# DC-Motor-DRV.net
KiCad netlist of a schematic drawn in Altium Designer
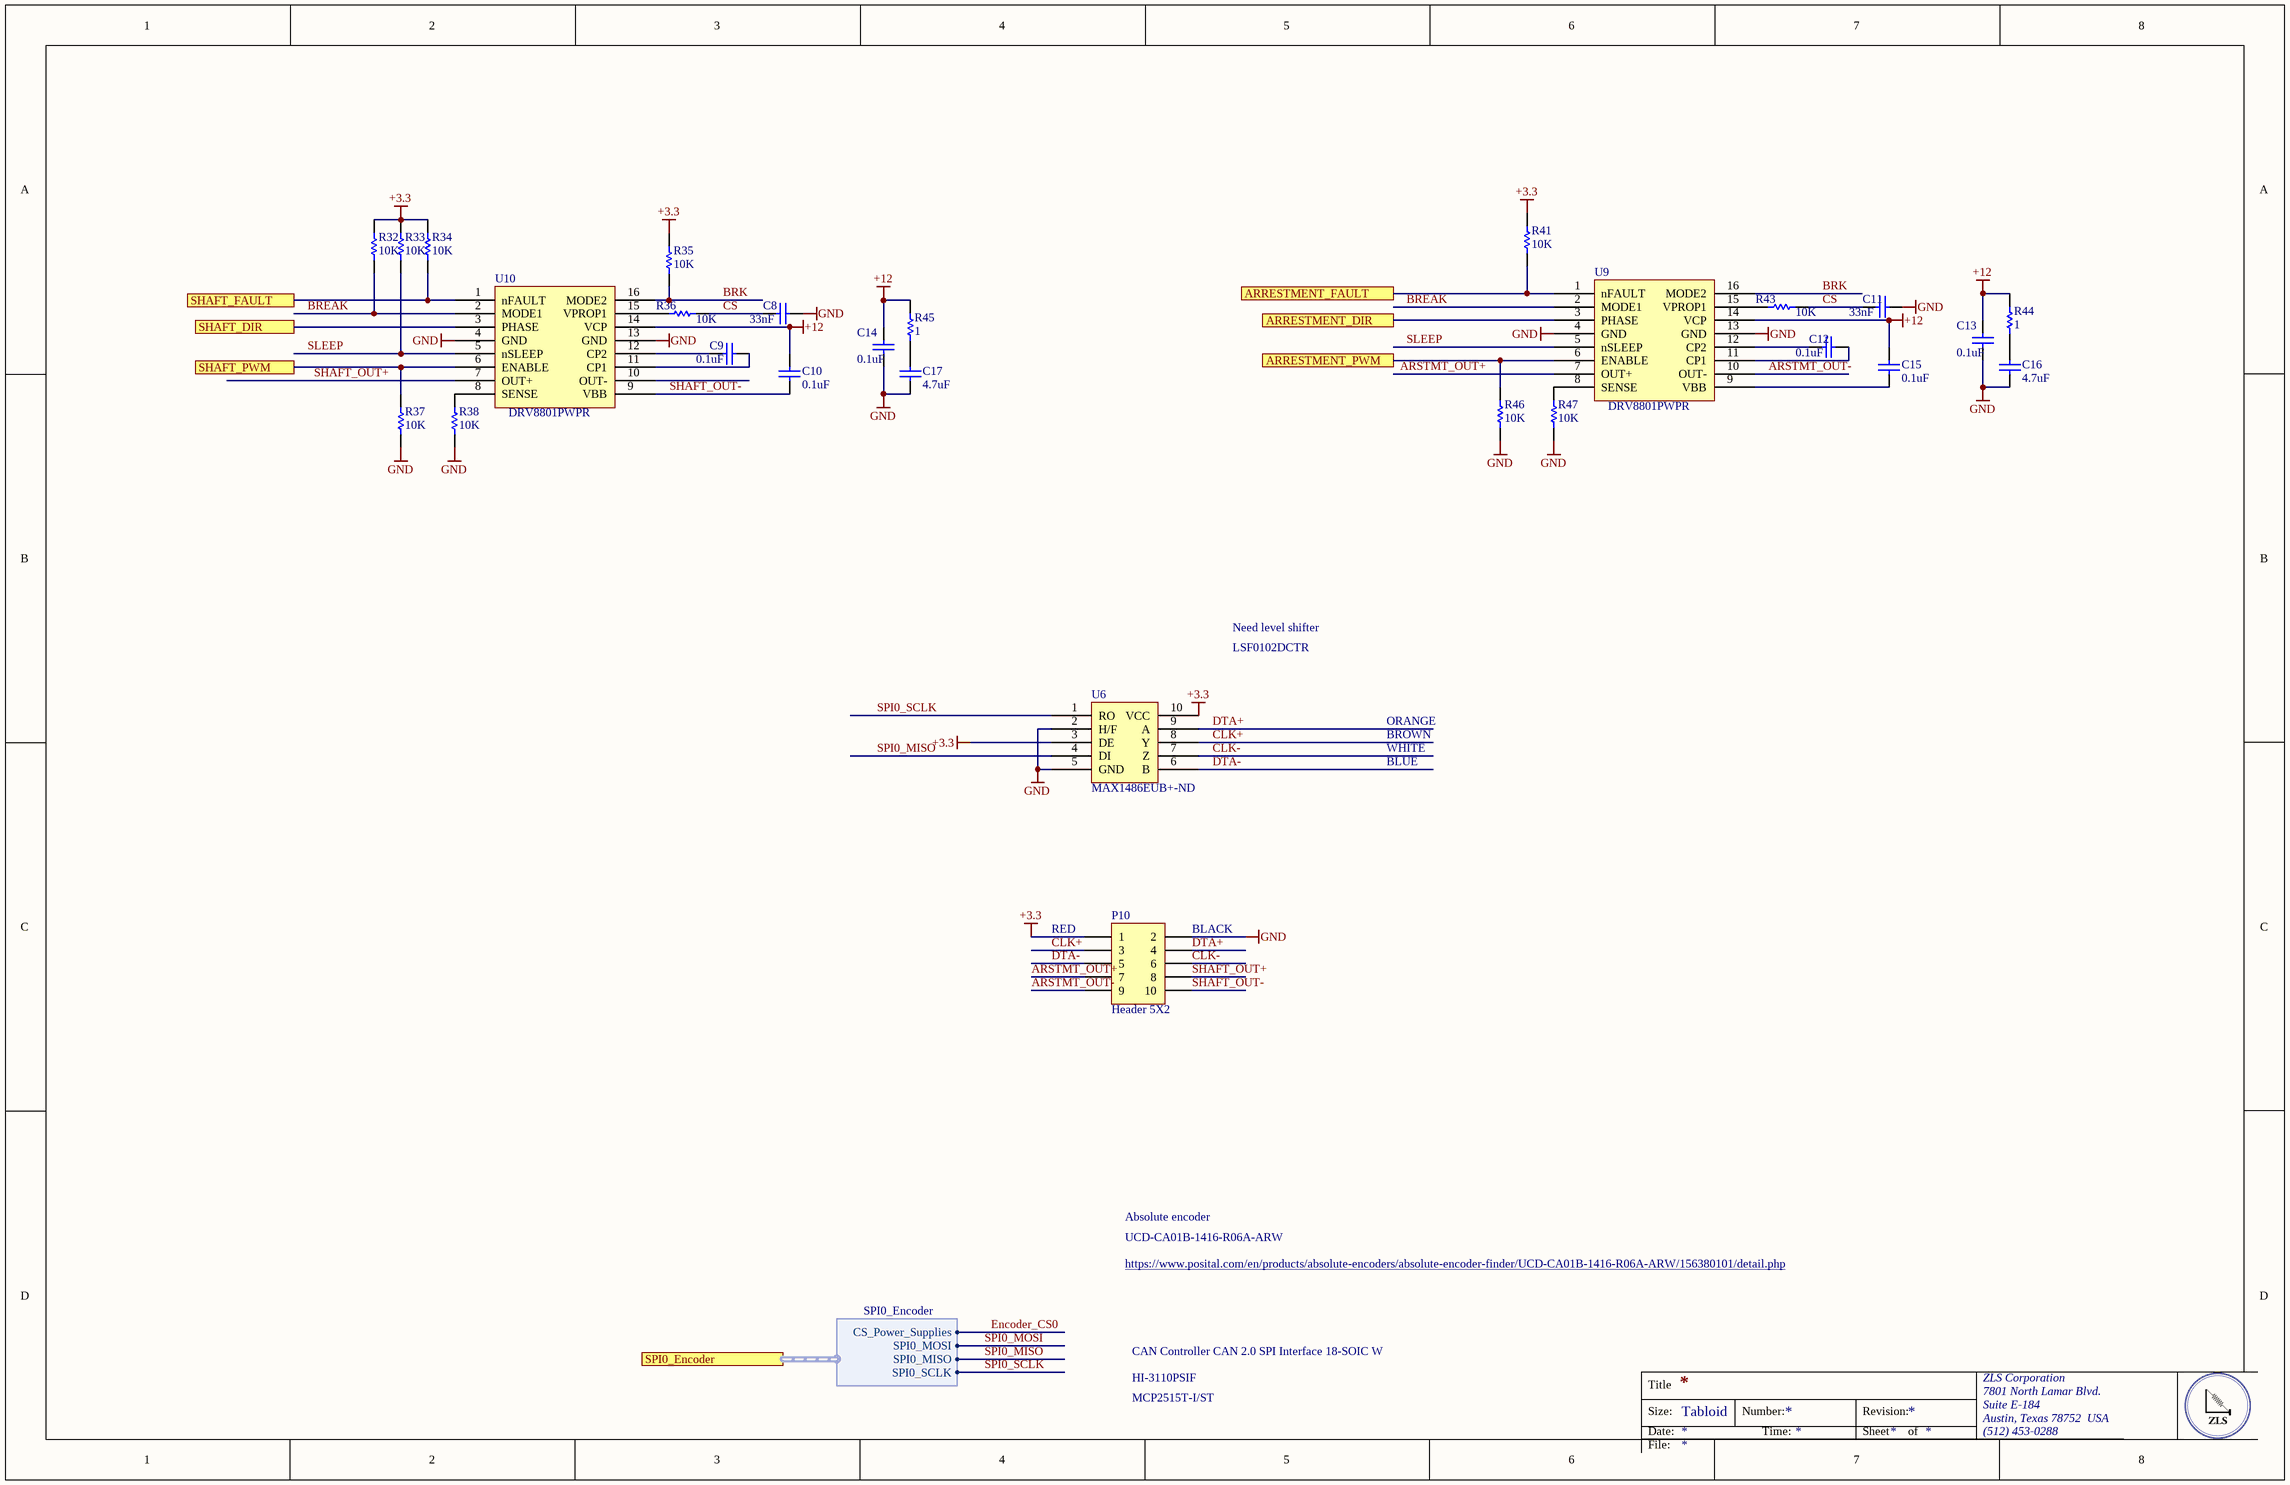
[diagram p0: DC-Motor-DRV.SchDoc]

(export (version "E")
  (design (tool "Eeschema 10.0.6"))
  (components
    (comp (ref "C8")
      (value "33nF")
      (footprint "CAPC0402(1005)60_L")
      (description "CAP CER 0.1UF 10V X7R 0402")
      (fields
        (field (name "MANUFACTURER") "Murata Electronics North America")
        (field (name "MANUFACTURER PART NUMBER") "GRM155R71A104KA01D")
      )
      (libsource (lib "Altium Content Vault") (part "CMP-1034-00252-1"))
    )
    (comp (ref "C9")
      (value "0.1uF")
      (footprint "CAPC0402(1005)60_L")
      (description "CAP CER 0.1UF 10V X7R 0402")
      (fields
        (field (name "MANUFACTURER") "Murata Electronics North America")
        (field (name "MANUFACTURER PART NUMBER") "GRM155R71A104KA01D")
      )
      (libsource (lib "Altium Content Vault") (part "CMP-1034-00252-1"))
    )
    (comp (ref "C10")
      (value "0.1uF")
      (footprint "CAPC0402(1005)60_L")
      (description "CAP CER 0.1UF 10V X7R 0402")
      (fields
        (field (name "MANUFACTURER") "Murata Electronics North America")
        (field (name "MANUFACTURER PART NUMBER") "GRM155R71A104KA01D")
      )
      (libsource (lib "Altium Content Vault") (part "CMP-1034-00252-1"))
    )
    (comp (ref "C11")
      (value "33nF")
      (footprint "CAPC0402(1005)60_L")
      (description "CAP CER 0.1UF 10V X7R 0402")
      (fields
        (field (name "MANUFACTURER") "Murata Electronics North America")
        (field (name "MANUFACTURER PART NUMBER") "GRM155R71A104KA01D")
      )
      (libsource (lib "Altium Content Vault") (part "CMP-1034-00252-1"))
    )
    (comp (ref "C12")
      (value "0.1uF")
      (footprint "CAPC0402(1005)60_L")
      (description "CAP CER 0.1UF 10V X7R 0402")
      (fields
        (field (name "MANUFACTURER") "Murata Electronics North America")
        (field (name "MANUFACTURER PART NUMBER") "GRM155R71A104KA01D")
      )
      (libsource (lib "Altium Content Vault") (part "CMP-1034-00252-1"))
    )
    (comp (ref "C13")
      (value "0.1uF")
      (footprint "CAPC0402(1005)60_L")
      (description "CAP CER 0.1UF 10V X7R 0402")
      (fields
        (field (name "MANUFACTURER") "Murata Electronics North America")
        (field (name "MANUFACTURER PART NUMBER") "GRM155R71A104KA01D")
      )
      (libsource (lib "Altium Content Vault") (part "CMP-1034-00252-1"))
    )
    (comp (ref "C14")
      (value "0.1uF")
      (footprint "CAPC0402(1005)60_L")
      (description "CAP CER 0.1UF 10V X7R 0402")
      (fields
        (field (name "MANUFACTURER") "Murata Electronics North America")
        (field (name "MANUFACTURER PART NUMBER") "GRM155R71A104KA01D")
      )
      (libsource (lib "Altium Content Vault") (part "CMP-1034-00252-1"))
    )
    (comp (ref "C15")
      (value "0.1uF")
      (footprint "CAPC0402(1005)60_L")
      (description "CAP CER 0.1UF 10V X7R 0402")
      (fields
        (field (name "MANUFACTURER") "Murata Electronics North America")
        (field (name "MANUFACTURER PART NUMBER") "GRM155R71A104KA01D")
      )
      (libsource (lib "Altium Content Vault") (part "CMP-1034-00252-1"))
    )
    (comp (ref "C16")
      (value "4.7uF")
      (footprint "CAPC0402(1005)60_L")
      (description "CAP CER 0.1UF 10V X7R 0402")
      (fields
        (field (name "MANUFACTURER") "Murata Electronics North America")
        (field (name "MANUFACTURER PART NUMBER") "GRM155R71A104KA01D")
      )
      (libsource (lib "Altium Content Vault") (part "CMP-1034-00252-1"))
    )
    (comp (ref "C17")
      (value "4.7uF")
      (footprint "CAPC0402(1005)60_L")
      (description "CAP CER 0.1UF 10V X7R 0402")
      (fields
        (field (name "MANUFACTURER") "Murata Electronics North America")
        (field (name "MANUFACTURER PART NUMBER") "GRM155R71A104KA01D")
      )
      (libsource (lib "Altium Content Vault") (part "CMP-1034-00252-1"))
    )
    (comp (ref "P10")
      (value "Header 5X2")
      (footprint "HDR2X5")
      (description "Header, 5-Pin, Dual row")
      (fields (field (name "PUBLISHER") "Altium Limited"))
      (libsource (lib "Miscellaneous Connectors") (part "Header 5X2"))
    )
    (comp (ref "R32")
      (value "10K")
      (footprint "RESC0402(1005)_M")
      (libsource (lib "Altium Content Vault") (part "CMP-1011-00651-1"))
    )
    (comp (ref "R33")
      (value "10K")
      (footprint "RESC0402(1005)_M")
      (libsource (lib "Altium Content Vault") (part "CMP-1011-00651-1"))
    )
    (comp (ref "R34")
      (value "10K")
      (footprint "RESC0402(1005)_M")
      (libsource (lib "Altium Content Vault") (part "CMP-1011-00651-1"))
    )
    (comp (ref "R35")
      (value "10K")
      (footprint "RESC0402(1005)_M")
      (libsource (lib "Altium Content Vault") (part "CMP-1011-00651-1"))
    )
    (comp (ref "R36")
      (value "10K")
      (footprint "RESC0402(1005)_M")
      (libsource (lib "Altium Content Vault") (part "CMP-1011-00651-1"))
    )
    (comp (ref "R37")
      (value "10K")
      (footprint "RESC0402(1005)_M")
      (libsource (lib "Altium Content Vault") (part "CMP-1011-00651-1"))
    )
    (comp (ref "R38")
      (value "10K")
      (footprint "RESC0402(1005)_M")
      (libsource (lib "Altium Content Vault") (part "CMP-1011-00651-1"))
    )
    (comp (ref "R41")
      (value "10K")
      (footprint "RESC0402(1005)_M")
      (libsource (lib "Altium Content Vault") (part "CMP-1011-00651-1"))
    )
    (comp (ref "R43")
      (value "10K")
      (footprint "RESC0402(1005)_M")
      (libsource (lib "Altium Content Vault") (part "CMP-1011-00651-1"))
    )
    (comp (ref "R44")
      (value "1")
      (footprint "RESC0402(1005)_M")
      (libsource (lib "Altium Content Vault") (part "CMP-1011-00651-1"))
    )
    (comp (ref "R45")
      (value "1")
      (footprint "RESC0402(1005)_M")
      (libsource (lib "Altium Content Vault") (part "CMP-1011-00651-1"))
    )
    (comp (ref "R46")
      (value "10K")
      (footprint "RESC0402(1005)_M")
      (libsource (lib "Altium Content Vault") (part "CMP-1011-00651-1"))
    )
    (comp (ref "R47")
      (value "10K")
      (footprint "RESC0402(1005)_M")
      (libsource (lib "Altium Content Vault") (part "CMP-1011-00651-1"))
    )
    (comp (ref "U6")
      (value "MAX1486EUB+")
      (footprint "MAX1486EUB+")
      (fields
        (field (name "SUPPLIER PART NUMBER 1") "MAX1486EUB+-ND")
        (field (name "MANUFACTURER") "Maxim Integrated")
        (field (name "BASE PART NUMBER") "MAX1486")
      )
      (libsource (lib "ZLS_Schematic_lib") (part "MAX1486EUB+"))
    )
    (comp (ref "U9")
      (value "DRV8801PWPR")
      (footprint "DRV8801PWPR")
      (fields (field (name "MANUFACTURER") "Texas Instruments") (field (name "BASE PART NUMBER") "DRV8801"))
      (libsource (lib "ZLS_Schematic_lib") (part "DRV8801PWPR"))
    )
    (comp (ref "U10")
      (value "DRV8801PWPR")
      (footprint "DRV8801PWPR")
      (fields (field (name "MANUFACTURER") "Texas Instruments") (field (name "BASE PART NUMBER") "DRV8801"))
      (libsource (lib "ZLS_Schematic_lib") (part "DRV8801PWPR"))
    )
  )
  (nets
    (net (code "2") (name "+3.3") (class "Default")
      (node (ref "P10") (pin "1") (pinfunction "1_1") (pintype "passive"))
      (node (ref "R32") (pin "2") (pinfunction "2_2") (pintype "passive"))
      (node (ref "R33") (pin "2") (pinfunction "2_2") (pintype "passive"))
      (node (ref "R34") (pin "2") (pinfunction "2_2") (pintype "passive"))
      (node (ref "R35") (pin "2") (pinfunction "2_2") (pintype "passive"))
      (node (ref "R41") (pin "2") (pinfunction "2_2") (pintype "passive"))
      (node (ref "U6") (pin "10") (pinfunction "VCC_10") (pintype "passive"))
      (node (ref "U6") (pin "3") (pinfunction "DE_3") (pintype "passive"))
    )
    (net (code "3") (name "+12") (class "Default")
      (node (ref "C10") (pin "2") (pinfunction "2_2") (pintype "passive"))
      (node (ref "C13") (pin "2") (pinfunction "2_2") (pintype "passive"))
      (node (ref "C14") (pin "2") (pinfunction "2_2") (pintype "passive"))
      (node (ref "C15") (pin "2") (pinfunction "2_2") (pintype "passive"))
      (node (ref "R44") (pin "2") (pinfunction "2_2") (pintype "passive"))
      (node (ref "R45") (pin "2") (pinfunction "2_2") (pintype "passive"))
      (node (ref "U10") (pin "14") (pinfunction "VCP_14") (pintype "passive"))
      (node (ref "U9") (pin "14") (pinfunction "VCP_14") (pintype "passive"))
    )
    (net (code "4") (name "/ARRESTMENT_DIR") (class "Default")
      (node (ref "U9") (pin "3") (pinfunction "PHASE_3") (pintype "passive"))
    )
    (net (code "5") (name "/ARRESTMENT_FAULT") (class "Default")
      (node (ref "R41") (pin "1") (pinfunction "1_1") (pintype "passive"))
      (node (ref "U9") (pin "1") (pinfunction "nFAULT_1") (pintype "passive"))
    )
    (net (code "6") (name "/ARRESTMENT_PWM") (class "Default")
      (node (ref "R46") (pin "2") (pinfunction "2_2") (pintype "passive"))
      (node (ref "U9") (pin "6") (pinfunction "ENABLE_6") (pintype "passive"))
    )
    (net (code "7") (name "/ARSTMT_OUT+") (class "Default")
      (node (ref "P10") (pin "7") (pinfunction "7_7") (pintype "passive"))
      (node (ref "U9") (pin "7") (pinfunction "OUT+_7") (pintype "passive"))
    )
    (net (code "8") (name "/ARSTMT_OUT-") (class "Default")
      (node (ref "P10") (pin "9") (pinfunction "9_9") (pintype "passive"))
      (node (ref "U9") (pin "10") (pinfunction "OUT-_10") (pintype "passive"))
    )
    (net (code "9") (name "/BREAK") (class "Default")
      (node (ref "R32") (pin "1") (pinfunction "1_1") (pintype "passive"))
      (node (ref "U10") (pin "2") (pinfunction "MODE1_2") (pintype "passive"))
      (node (ref "U9") (pin "2") (pinfunction "MODE1_2") (pintype "passive"))
    )
    (net (code "10") (name "/BRK") (class "Default")
      (node (ref "R35") (pin "1") (pinfunction "1_1") (pintype "passive"))
      (node (ref "U10") (pin "16") (pinfunction "MODE2_16") (pintype "passive"))
      (node (ref "U9") (pin "16") (pinfunction "MODE2_16") (pintype "passive"))
    )
    (net (code "11") (name "/CLK+") (class "Default")
      (node (ref "P10") (pin "3") (pinfunction "3_3") (pintype "passive"))
      (node (ref "U6") (pin "8") (pinfunction "Y_8") (pintype "passive"))
    )
    (net (code "12") (name "/CLK-") (class "Default")
      (node (ref "P10") (pin "6") (pinfunction "6_6") (pintype "passive"))
      (node (ref "U6") (pin "7") (pinfunction "Z_7") (pintype "passive"))
    )
    (net (code "13") (name "/CS") (class "Default")
      (node (ref "C11") (pin "1") (pinfunction "1_1") (pintype "passive"))
      (node (ref "C8") (pin "1") (pinfunction "1_1") (pintype "passive"))
      (node (ref "R36") (pin "2") (pinfunction "2_2") (pintype "passive"))
      (node (ref "R43") (pin "2") (pinfunction "2_2") (pintype "passive"))
    )
    (net (code "14") (name "/DTA+") (class "Default")
      (node (ref "P10") (pin "4") (pinfunction "4_4") (pintype "passive"))
      (node (ref "U6") (pin "9") (pinfunction "A_9") (pintype "passive"))
    )
    (net (code "15") (name "/DTA-") (class "Default")
      (node (ref "P10") (pin "5") (pinfunction "5_5") (pintype "passive"))
      (node (ref "U6") (pin "6") (pinfunction "B_6") (pintype "passive"))
    )
    (net (code "17") (name "/SHAFT_DIR") (class "Default")
      (node (ref "U10") (pin "3") (pinfunction "PHASE_3") (pintype "passive"))
    )
    (net (code "18") (name "/SHAFT_FAULT") (class "Default")
      (node (ref "R34") (pin "1") (pinfunction "1_1") (pintype "passive"))
      (node (ref "U10") (pin "1") (pinfunction "nFAULT_1") (pintype "passive"))
    )
    (net (code "19") (name "/SHAFT_OUT+") (class "Default")
      (node (ref "P10") (pin "8") (pinfunction "8_8") (pintype "passive"))
      (node (ref "U10") (pin "7") (pinfunction "OUT+_7") (pintype "passive"))
    )
    (net (code "20") (name "/SHAFT_OUT-") (class "Default")
      (node (ref "C10") (pin "1") (pinfunction "1_1") (pintype "passive"))
      (node (ref "P10") (pin "10") (pinfunction "10_10") (pintype "passive"))
      (node (ref "U10") (pin "9") (pinfunction "VBB_9") (pintype "passive"))
    )
    (net (code "21") (name "/SHAFT_PWM") (class "Default")
      (node (ref "R37") (pin "2") (pinfunction "2_2") (pintype "passive"))
      (node (ref "U10") (pin "6") (pinfunction "ENABLE_6") (pintype "passive"))
    )
    (net (code "22") (name "/SLEEP") (class "Default")
      (node (ref "R33") (pin "1") (pinfunction "1_1") (pintype "passive"))
      (node (ref "U10") (pin "5") (pinfunction "nSLEEP_5") (pintype "passive"))
      (node (ref "U9") (pin "5") (pinfunction "nSLEEP_5") (pintype "passive"))
    )
    (net (code "23") (name "/SPI0_MISO") (class "Default")
      (node (ref "U6") (pin "4") (pinfunction "DI_4") (pintype "passive"))
    )
    (net (code "25") (name "/SPI0_SCLK") (class "Default")
      (node (ref "U6") (pin "1") (pinfunction "RO_1") (pintype "passive"))
    )
    (net (code "27") (name "GND") (class "Default")
      (node (ref "C11") (pin "2") (pinfunction "2_2") (pintype "passive"))
      (node (ref "C13") (pin "1") (pinfunction "1_1") (pintype "passive"))
      (node (ref "C14") (pin "1") (pinfunction "1_1") (pintype "passive"))
      (node (ref "C16") (pin "1") (pinfunction "1_1") (pintype "passive"))
      (node (ref "C17") (pin "1") (pinfunction "1_1") (pintype "passive"))
      (node (ref "C8") (pin "2") (pinfunction "2_2") (pintype "passive"))
      (node (ref "P10") (pin "2") (pinfunction "2_2") (pintype "passive"))
      (node (ref "R37") (pin "1") (pinfunction "1_1") (pintype "passive"))
      (node (ref "R38") (pin "1") (pinfunction "1_1") (pintype "passive"))
      (node (ref "R46") (pin "1") (pinfunction "1_1") (pintype "passive"))
      (node (ref "R47") (pin "1") (pinfunction "1_1") (pintype "passive"))
      (node (ref "U10") (pin "13") (pinfunction "GND_13") (pintype "passive"))
      (node (ref "U10") (pin "4") (pinfunction "GND_4") (pintype "passive"))
      (node (ref "U6") (pin "2") (pinfunction "H/F_2") (pintype "passive"))
      (node (ref "U6") (pin "5") (pinfunction "GND_5") (pintype "passive"))
      (node (ref "U9") (pin "13") (pinfunction "GND_13") (pintype "passive"))
      (node (ref "U9") (pin "4") (pinfunction "GND_4") (pintype "passive"))
    )
    (net (code "28") (name "Net-(C16-Pad2)") (class "Default")
      (node (ref "C16") (pin "2") (pinfunction "2_2") (pintype "passive"))
      (node (ref "R44") (pin "1") (pinfunction "1_1") (pintype "passive"))
    )
    (net (code "29") (name "Net-(C17-Pad2)") (class "Default")
      (node (ref "C17") (pin "2") (pinfunction "2_2") (pintype "passive"))
      (node (ref "R45") (pin "1") (pinfunction "1_1") (pintype "passive"))
    )
    (net (code "30") (name "Net-(U9-CP1)") (class "Default")
      (node (ref "C12") (pin "1") (pinfunction "1_1") (pintype "passive"))
      (node (ref "U9") (pin "11") (pinfunction "CP1_11") (pintype "passive"))
    )
    (net (code "31") (name "Net-(U9-CP2)") (class "Default")
      (node (ref "C12") (pin "2") (pinfunction "2_2") (pintype "passive"))
      (node (ref "U9") (pin "12") (pinfunction "CP2_12") (pintype "passive"))
    )
    (net (code "32") (name "Net-(U9-SENSE)") (class "Default")
      (node (ref "R47") (pin "2") (pinfunction "2_2") (pintype "passive"))
      (node (ref "U9") (pin "8") (pinfunction "SENSE_8") (pintype "passive"))
    )
    (net (code "33") (name "Net-(U9-VBB)") (class "Default")
      (node (ref "C15") (pin "1") (pinfunction "1_1") (pintype "passive"))
      (node (ref "U9") (pin "9") (pinfunction "VBB_9") (pintype "passive"))
    )
    (net (code "34") (name "Net-(U9-VPROP1)") (class "Default")
      (node (ref "R43") (pin "1") (pinfunction "1_1") (pintype "passive"))
      (node (ref "U9") (pin "15") (pinfunction "VPROP1_15") (pintype "passive"))
    )
    (net (code "35") (name "Net-(U10-CP1)") (class "Default")
      (node (ref "C9") (pin "1") (pinfunction "1_1") (pintype "passive"))
      (node (ref "U10") (pin "11") (pinfunction "CP1_11") (pintype "passive"))
    )
    (net (code "36") (name "Net-(U10-CP2)") (class "Default")
      (node (ref "C9") (pin "2") (pinfunction "2_2") (pintype "passive"))
      (node (ref "U10") (pin "12") (pinfunction "CP2_12") (pintype "passive"))
    )
    (net (code "37") (name "Net-(U10-SENSE)") (class "Default")
      (node (ref "R38") (pin "2") (pinfunction "2_2") (pintype "passive"))
      (node (ref "U10") (pin "8") (pinfunction "SENSE_8") (pintype "passive"))
    )
    (net (code "38") (name "Net-(U10-VPROP1)") (class "Default")
      (node (ref "R36") (pin "1") (pinfunction "1_1") (pintype "passive"))
      (node (ref "U10") (pin "15") (pinfunction "VPROP1_15") (pintype "passive"))
    )
    (net (code "39") (name "unconnected-(U10-OUT--Pad10)") (class "Default")
      (node (ref "U10") (pin "10") (pinfunction "OUT-_10") (pintype "passive"))
    )
  )
)
